# power.net
KiCad netlist of a schematic drawn in Altium Designer
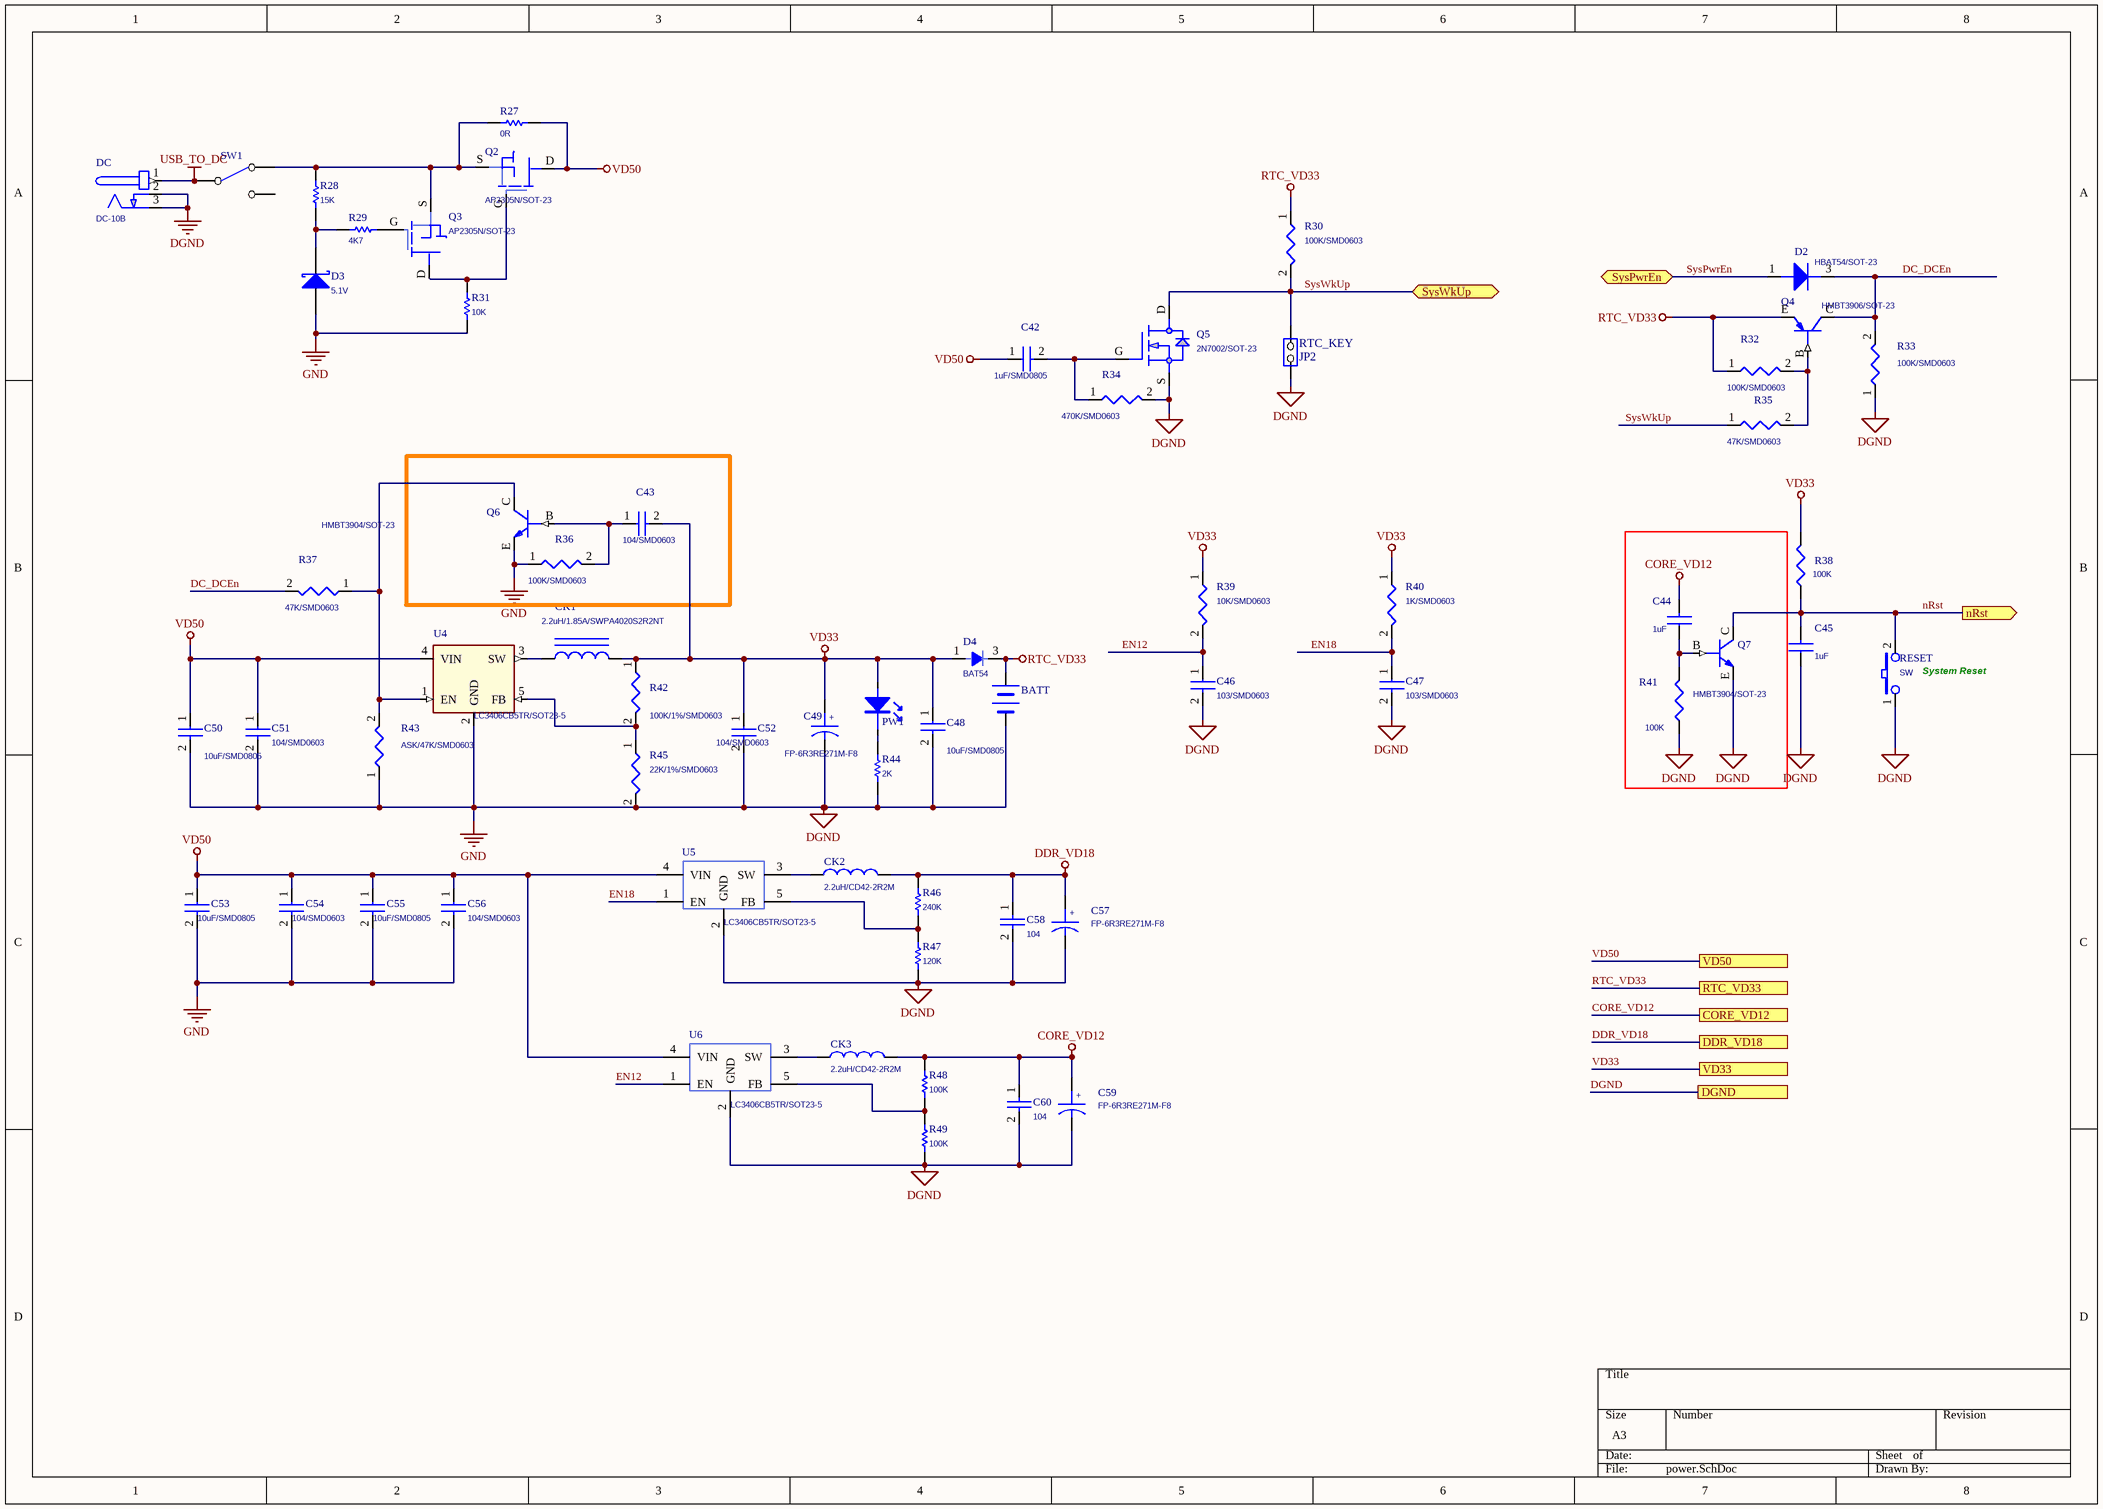
[diagram p0: power.SchDoc]

(export (version "E")
  (design (tool "Eeschema 10.0.6"))
  (components
    (comp (ref "BATT") (value "BATTERY") (footprint "MS621") (libsource (lib "GT2440原理图库") (part "BATTERY")))
    (comp (ref "C42") (value "1uF/SMD0805") (footprint "C0805") (libsource (lib "*") (part "C/SMD0805")))
    (comp (ref "C43") (value "104/SMD0603") (footprint "0603C") (libsource (lib "*") (part "C/SMD0603")))
    (comp (ref "C44") (value "1uF") (footprint "0603C") (libsource (lib "*") (part "CAP NP_Dup1")))
    (comp (ref "C45") (value "1uF") (footprint "0603C") (libsource (lib "*") (part "CAP NP_Dup1")))
    (comp (ref "C46") (value "103/SMD0603") (footprint "0603C") (libsource (lib "*") (part "C/SMD0603")))
    (comp (ref "C47") (value "103/SMD0603") (footprint "0603C") (libsource (lib "*") (part "C/SMD0603")))
    (comp (ref "C48") (value "10uF/SMD0805") (footprint "C0805") (libsource (lib "*") (part "C/SMD0805")))
    (comp (ref "C49")
      (value "FP-6R3RE271M-F8")
      (footprint "6R3RE271M")
      (libsource (lib "*") (part "CAP POL"))
    )
    (comp (ref "C50") (value "10uF/SMD0805") (footprint "C0805") (libsource (lib "*") (part "C/SMD0805")))
    (comp (ref "C51") (value "104/SMD0603") (footprint "0603C") (libsource (lib "*") (part "C/SMD0603")))
    (comp (ref "C52") (value "104/SMD0603") (footprint "0603C") (libsource (lib "*") (part "C/SMD0603")))
    (comp (ref "C53") (value "10uF/SMD0805") (footprint "C0805") (libsource (lib "*") (part "C/SMD1206")))
    (comp (ref "C54") (value "104/SMD0603") (footprint "0603C") (libsource (lib "*") (part "C/SMD0603")))
    (comp (ref "C55") (value "10uF/SMD0805") (footprint "C0805") (libsource (lib "*") (part "C/SMD1206")))
    (comp (ref "C56") (value "104/SMD0603") (footprint "0603C") (libsource (lib "*") (part "C/SMD0603")))
    (comp (ref "C57")
      (value "FP-6R3RE271M-F8")
      (footprint "6R3RE271M")
      (libsource (lib "*") (part "CAP POL"))
    )
    (comp (ref "C58")
      (value "104")
      (footprint "0603C")
      (description "Capacitor")
      (libsource (lib "MYSTM32") (part "CAP"))
    )
    (comp (ref "C59")
      (value "FP-6R3RE271M-F8")
      (footprint "6R3RE271M")
      (libsource (lib "*") (part "CAP POL"))
    )
    (comp (ref "C60")
      (value "104")
      (footprint "0603C")
      (description "Capacitor")
      (libsource (lib "MYSTM32") (part "CAP"))
    )
    (comp (ref "CK1")
      (value "2.2uH/1.85A/SWPA4020S2R2NT")
      (footprint "C1210_M")
      (libsource (lib "*") (part "INDUCTOR IRON"))
    )
    (comp (ref "CK2")
      (value "2.2uH/CD42-2R2M")
      (footprint "C1210_M")
      (libsource (lib "GT2440原理图库") (part "INDUCTOR1"))
    )
    (comp (ref "CK3")
      (value "2.2uH/CD42-2R2M")
      (footprint "C1210_M")
      (libsource (lib "GT2440原理图库") (part "INDUCTOR1"))
    )
    (comp (ref "D2") (value "HBAT54/SOT-23") (libsource (lib "changyong") (part "HBAT54/SOT-23")))
    (comp (ref "D3")
      (value "5.1V")
      (footprint "SOD-123_1N5819HW")
      (description "Schottky Rectifier")
      (fields (field (name "PUBLISHER") "Altium Limited"))
      (libsource (lib "Miscellaneous Devices") (part "Diode 10TQ035"))
    )
    (comp (ref "D4") (value "BAT54") (footprint "BAT54") (libsource (lib "n32905") (part "BAT54")))
    (comp (ref "DC") (value "DC-10B") (footprint "DC-JACK") (libsource (lib "STM32F107VCT") (part "PJ202A")))
    (comp (ref "PW1") (value "red") (footprint "LED-0603") (libsource (lib "GT2440原理图库") (part "LED")))
    (comp (ref "Q2")
      (value "AP2305N/SOT-23")
      (footprint "AP2305N_SOT23")
      (libsource (lib "changyong") (part "AP2305N/SOT-23"))
    )
    (comp (ref "Q3")
      (value "AP2305N/SOT-23")
      (footprint "AP2305N_SOT23")
      (libsource (lib "changyong") (part "AP2305N/SOT-23"))
    )
    (comp (ref "Q4")
      (value "HMBT3906/SOT-23")
      (footprint "SOT-23_HMBT3906")
      (libsource (lib "*") (part "HMBT3906/SOT-23"))
    )
    (comp (ref "Q5")
      (value "2N7002/SOT-23")
      (footprint "SOT-23_H2N7002")
      (libsource (lib "*") (part "2N7002/SOT-23_Dup1"))
    )
    (comp (ref "Q6")
      (value "HMBT3904/SOT-23")
      (footprint "SOT-23_HMBT3904")
      (libsource (lib "*") (part "HMBT3904/SOT-23"))
    )
    (comp (ref "Q7")
      (value "HMBT3904/SOT-23")
      (footprint "SOT-23_HMBT3904")
      (libsource (lib "changyong") (part "HMBT3904/SOT-23"))
    )
    (comp (ref "R27")
      (value "0R")
      (footprint "0603C")
      (description "Resistor")
      (fields (field (name "PUBLISHER") "Altium Limited"))
      (libsource (lib "STM32F107VCT") (part "res1"))
    )
    (comp (ref "R28")
      (value "15K")
      (footprint "0603C")
      (description "Resistor")
      (fields (field (name "PUBLISHER") "Altium Limited"))
      (libsource (lib "STM32F107VCT") (part "res1"))
    )
    (comp (ref "R29")
      (value "4K7")
      (footprint "0603C")
      (description "Resistor")
      (fields (field (name "PUBLISHER") "Altium Limited"))
      (libsource (lib "STM32F107VCT") (part "res1"))
    )
    (comp (ref "R30") (value "100K/SMD0603") (footprint "0603R") (libsource (lib "*") (part "R/SMD0603")))
    (comp (ref "R31")
      (value "10K")
      (footprint "0603C")
      (description "Resistor")
      (fields (field (name "PUBLISHER") "Altium Limited"))
      (libsource (lib "STM32F107VCT") (part "res1"))
    )
    (comp (ref "R32") (value "100K/SMD0603") (footprint "0603R") (libsource (lib "*") (part "R/SMD0603")))
    (comp (ref "R33") (value "100K/SMD0603") (footprint "0603R") (libsource (lib "*") (part "R/SMD0603")))
    (comp (ref "R34") (value "470K/SMD0603") (footprint "0603R") (libsource (lib "*") (part "R/SMD0603")))
    (comp (ref "R35") (value "47K/SMD0603") (footprint "0603R") (libsource (lib "*") (part "R/SMD0603")))
    (comp (ref "R36") (value "100K/SMD0603") (footprint "0603R") (libsource (lib "*") (part "R/SMD0603")))
    (comp (ref "R37") (value "47K/SMD0603") (footprint "0603R") (libsource (lib "*") (part "R/SMD0603")))
    (comp (ref "R38") (value "100K") (footprint "0603R") (libsource (lib "*") (part "R_Dup1")))
    (comp (ref "R39") (value "10K/SMD0603") (footprint "0603R") (libsource (lib "*") (part "R/SMD0603")))
    (comp (ref "R40") (value "1K/SMD0603") (footprint "0603R") (libsource (lib "*") (part "R/SMD0603")))
    (comp (ref "R41") (value "100K") (footprint "0603R") (libsource (lib "*") (part "R_Dup1")))
    (comp (ref "R42") (value "100K/1%/SMD0603") (footprint "0603R") (libsource (lib "*") (part "R/SMD0603")))
    (comp (ref "R43") (value "ASK/47K/SMD0603") (footprint "0603R") (libsource (lib "*") (part "R/SMD0603")))
    (comp (ref "R44")
      (value "2K")
      (footprint "0603R")
      (description "Resistor")
      (fields (field (name "PUBLISHER") "Altium Limited"))
      (libsource (lib "STM32F107VCT") (part "res1"))
    )
    (comp (ref "R45") (value "22K/1%/SMD0603") (footprint "0603R") (libsource (lib "*") (part "R/SMD0603")))
    (comp (ref "R46")
      (value "240K")
      (footprint "0603R")
      (description "Resistor")
      (fields (field (name "PUBLISHER") "Altium Limited"))
      (libsource (lib "STM32F107VCT") (part "res1"))
    )
    (comp (ref "R47")
      (value "120K")
      (footprint "0603R")
      (description "Resistor")
      (fields (field (name "PUBLISHER") "Altium Limited"))
      (libsource (lib "STM32F107VCT") (part "res1"))
    )
    (comp (ref "R48")
      (value "100K")
      (footprint "0603R")
      (description "Resistor")
      (fields (field (name "PUBLISHER") "Altium Limited"))
      (libsource (lib "STM32F107VCT") (part "res1"))
    )
    (comp (ref "R49")
      (value "100K")
      (footprint "0603R")
      (description "Resistor")
      (fields (field (name "PUBLISHER") "Altium Limited"))
      (libsource (lib "STM32F107VCT") (part "res1"))
    )
    (comp (ref "RESET") (value "SW") (footprint "SW-PB2") (libsource (lib "GT2440原理图库") (part "SW_PUSH")))
    (comp (ref "RTC_KEY") (value "JP2") (footprint "mhdr1x2") (libsource (lib "STM32F103VBH6") (part "JP2")))
    (comp (ref "SW1") (value "~") (footprint "SS-12D07") (libsource (lib "GT2440原理图库") (part "SW SPDT")))
    (comp (ref "U4")
      (value "LC3406CB5TR/SOT23-5")
      (footprint "SOT-23-5")
      (libsource (lib "*") (part "LC3406CB5TR/SOT23-5"))
    )
    (comp (ref "U5")
      (value "LC3406CB5TR/SOT23-5")
      (footprint "SOT-23-5")
      (libsource (lib "n32905") (part "LC3406CB5TR/SOT23-5"))
    )
    (comp (ref "U6")
      (value "LC3406CB5TR/SOT23-5")
      (footprint "SOT-23-5")
      (libsource (lib "n32905") (part "LC3406CB5TR/SOT23-5"))
    )
  )
  (nets
    (net (code "1") (name "/DC_DCEn") (class "Default")
      (node (ref "D2") (pin "3") (pinfunction "3_3") (pintype "passive"))
      (node (ref "Q4") (pin "C") (pinfunction "COLLECTOR_C") (pintype "passive"))
      (node (ref "R33") (pin "2") (pinfunction "2_2") (pintype "passive"))
      (node (ref "R37") (pin "2") (pinfunction "2_2") (pintype "passive"))
    )
    (net (code "2") (name "/EN12") (class "Default")
      (node (ref "C46") (pin "1") (pinfunction "1_1") (pintype "passive"))
      (node (ref "R39") (pin "2") (pinfunction "2_2") (pintype "passive"))
      (node (ref "U6") (pin "1") (pinfunction "EN_1") (pintype "passive"))
    )
    (net (code "3") (name "/EN18") (class "Default")
      (node (ref "C47") (pin "1") (pinfunction "1_1") (pintype "passive"))
      (node (ref "R40") (pin "2") (pinfunction "2_2") (pintype "passive"))
      (node (ref "U5") (pin "1") (pinfunction "EN_1") (pintype "passive"))
    )
    (net (code "4") (name "/SysPwrEn") (class "Default")
      (node (ref "D2") (pin "1") (pinfunction "1_1") (pintype "passive"))
    )
    (net (code "5") (name "/SysWkUp") (class "Default")
      (node (ref "Q5") (pin "D") (pinfunction "D_D") (pintype "passive"))
      (node (ref "R30") (pin "2") (pinfunction "2_2") (pintype "passive"))
      (node (ref "R35") (pin "1") (pinfunction "1_1") (pintype "passive"))
      (node (ref "RTC_KEY") (pin "2") (pinfunction "NO_2") (pintype "passive"))
    )
    (net (code "6") (name "/nRst") (class "Default")
      (node (ref "C45") (pin "2") (pinfunction "2_2") (pintype "passive"))
      (node (ref "Q7") (pin "C") (pinfunction "COLLECTOR_C") (pintype "passive"))
      (node (ref "R38") (pin "2") (pinfunction "2_2") (pintype "passive"))
      (node (ref "RESET") (pin "2") (pinfunction "2_2") (pintype "passive"))
    )
    (net (code "7") (name "CORE_VD12") (class "Default")
      (node (ref "C44") (pin "2") (pinfunction "2_2") (pintype "passive"))
      (node (ref "C59") (pin "1") (pinfunction "1_1") (pintype "passive"))
      (node (ref "C60") (pin "1") (pinfunction "1_1") (pintype "passive"))
      (node (ref "CK3") (pin "2") (pinfunction "2_2") (pintype "passive"))
      (node (ref "R48") (pin "2") (pinfunction "2_2") (pintype "passive"))
    )
    (net (code "8") (name "DDR_VD18") (class "Default")
      (node (ref "C57") (pin "1") (pinfunction "1_1") (pintype "passive"))
      (node (ref "C58") (pin "1") (pinfunction "1_1") (pintype "passive"))
      (node (ref "CK2") (pin "2") (pinfunction "2_2") (pintype "passive"))
      (node (ref "R46") (pin "2") (pinfunction "2_2") (pintype "passive"))
    )
    (net (code "9") (name "DGND") (class "Default")
      (node (ref "BATT") (pin "2") (pintype "passive"))
      (node (ref "C45") (pin "1") (pinfunction "1_1") (pintype "passive"))
      (node (ref "C46") (pin "2") (pinfunction "2_2") (pintype "passive"))
      (node (ref "C47") (pin "2") (pinfunction "2_2") (pintype "passive"))
      (node (ref "C48") (pin "2") (pinfunction "2_2") (pintype "passive"))
      (node (ref "C49") (pin "2") (pinfunction "2_2") (pintype "passive"))
      (node (ref "C50") (pin "2") (pinfunction "2_2") (pintype "passive"))
      (node (ref "C51") (pin "2") (pinfunction "2_2") (pintype "passive"))
      (node (ref "C52") (pin "2") (pinfunction "2_2") (pintype "passive"))
      (node (ref "C53") (pin "2") (pinfunction "2_2") (pintype "passive"))
      (node (ref "C54") (pin "2") (pinfunction "2_2") (pintype "passive"))
      (node (ref "C55") (pin "2") (pinfunction "2_2") (pintype "passive"))
      (node (ref "C56") (pin "2") (pinfunction "2_2") (pintype "passive"))
      (node (ref "C57") (pin "2") (pinfunction "2_2") (pintype "passive"))
      (node (ref "C58") (pin "2") (pinfunction "2_2") (pintype "passive"))
      (node (ref "C59") (pin "2") (pinfunction "2_2") (pintype "passive"))
      (node (ref "C60") (pin "2") (pinfunction "2_2") (pintype "passive"))
      (node (ref "D3") (pin "2") (pinfunction "A_2") (pintype "passive"))
      (node (ref "DC") (pin "2") (pinfunction "GND_2") (pintype "passive"))
      (node (ref "DC") (pin "3") (pinfunction "GND_3") (pintype "passive"))
      (node (ref "Q5") (pin "S") (pinfunction "S_S") (pintype "passive"))
      (node (ref "Q6") (pin "E") (pinfunction "EMITTER_E") (pintype "passive"))
      (node (ref "Q7") (pin "E") (pinfunction "EMITTER_E") (pintype "passive"))
      (node (ref "R31") (pin "1") (pinfunction "1_1") (pintype "passive"))
      (node (ref "R33") (pin "1") (pinfunction "1_1") (pintype "passive"))
      (node (ref "R34") (pin "2") (pinfunction "2_2") (pintype "passive"))
      (node (ref "R36") (pin "1") (pinfunction "1_1") (pintype "passive"))
      (node (ref "R41") (pin "2") (pinfunction "2_2") (pintype "passive"))
      (node (ref "R43") (pin "1") (pinfunction "1_1") (pintype "passive"))
      (node (ref "R44") (pin "1") (pinfunction "1_1") (pintype "passive"))
      (node (ref "R45") (pin "2") (pinfunction "2_2") (pintype "passive"))
      (node (ref "R47") (pin "1") (pinfunction "1_1") (pintype "passive"))
      (node (ref "R49") (pin "1") (pinfunction "1_1") (pintype "passive"))
      (node (ref "RESET") (pin "1") (pinfunction "1_1") (pintype "passive"))
      (node (ref "RTC_KEY") (pin "1") (pinfunction "COMMON_1") (pintype "passive"))
      (node (ref "U4") (pin "2") (pinfunction "GND_2") (pintype "power_in"))
      (node (ref "U5") (pin "2") (pinfunction "GND_2") (pintype "passive"))
      (node (ref "U6") (pin "2") (pinfunction "GND_2") (pintype "passive"))
    )
    (net (code "10") (name "Net-(C42-Pad2)") (class "Default")
      (node (ref "C42") (pin "2") (pinfunction "2_2") (pintype "passive"))
      (node (ref "Q5") (pin "G") (pinfunction "G_G") (pintype "passive"))
      (node (ref "R34") (pin "1") (pinfunction "1_1") (pintype "passive"))
    )
    (net (code "11") (name "Net-(D3-K)") (class "Default")
      (node (ref "D3") (pin "1") (pinfunction "K_1") (pintype "passive"))
      (node (ref "R28") (pin "1") (pinfunction "1_1") (pintype "passive"))
      (node (ref "R29") (pin "2") (pinfunction "2_2") (pintype "passive"))
    )
    (net (code "12") (name "Net-(PW1-Pad2)") (class "Default")
      (node (ref "PW1") (pin "2") (pinfunction "2_2") (pintype "passive"))
      (node (ref "R44") (pin "2") (pinfunction "2_2") (pintype "passive"))
    )
    (net (code "13") (name "Net-(Q2-2)") (class "Default")
      (node (ref "Q2") (pin "G") (pinfunction "2_G") (pintype "passive"))
      (node (ref "Q3") (pin "D") (pinfunction "1_D") (pintype "passive"))
      (node (ref "R31") (pin "2") (pinfunction "2_2") (pintype "passive"))
    )
    (net (code "14") (name "Net-(Q2-3)") (class "Default")
      (node (ref "Q2") (pin "S") (pinfunction "3_S") (pintype "passive"))
      (node (ref "Q3") (pin "S") (pinfunction "3_S") (pintype "passive"))
      (node (ref "R27") (pin "2") (pinfunction "2_2") (pintype "passive"))
      (node (ref "R28") (pin "2") (pinfunction "2_2") (pintype "passive"))
      (node (ref "SW1") (pin "2") (pinfunction "NC_2") (pintype "passive"))
    )
    (net (code "15") (name "Net-(Q3-2)") (class "Default")
      (node (ref "Q3") (pin "G") (pinfunction "2_G") (pintype "passive"))
      (node (ref "R29") (pin "1") (pinfunction "1_1") (pintype "passive"))
    )
    (net (code "16") (name "Net-(Q4-BASE)") (class "Default")
      (node (ref "Q4") (pin "B") (pinfunction "BASE_B") (pintype "input"))
      (node (ref "R32") (pin "2") (pinfunction "2_2") (pintype "passive"))
      (node (ref "R35") (pin "2") (pinfunction "2_2") (pintype "passive"))
    )
    (net (code "17") (name "Net-(Q6-BASE)") (class "Default")
      (node (ref "C43") (pin "1") (pinfunction "1_1") (pintype "passive"))
      (node (ref "Q6") (pin "B") (pinfunction "BASE_B") (pintype "input"))
      (node (ref "R36") (pin "2") (pinfunction "2_2") (pintype "passive"))
    )
    (net (code "18") (name "Net-(Q6-COLLECTOR)") (class "Default")
      (node (ref "Q6") (pin "C") (pinfunction "COLLECTOR_C") (pintype "passive"))
      (node (ref "R37") (pin "1") (pinfunction "1_1") (pintype "passive"))
      (node (ref "R43") (pin "2") (pinfunction "2_2") (pintype "passive"))
      (node (ref "U4") (pin "1") (pinfunction "EN_1") (pintype "input"))
    )
    (net (code "19") (name "Net-(Q7-BASE)") (class "Default")
      (node (ref "C44") (pin "1") (pinfunction "1_1") (pintype "passive"))
      (node (ref "Q7") (pin "B") (pinfunction "BASE_B") (pintype "input"))
      (node (ref "R41") (pin "1") (pinfunction "1_1") (pintype "passive"))
    )
    (net (code "20") (name "Net-(U4-FB)") (class "Default")
      (node (ref "R42") (pin "2") (pinfunction "2_2") (pintype "passive"))
      (node (ref "R45") (pin "1") (pinfunction "1_1") (pintype "passive"))
      (node (ref "U4") (pin "5") (pinfunction "FB_5") (pintype "input"))
    )
    (net (code "21") (name "Net-(U4-SW)") (class "Default")
      (node (ref "CK1") (pin "1") (pinfunction "1_1") (pintype "passive"))
      (node (ref "U4") (pin "3") (pinfunction "SW_3") (pintype "output"))
    )
    (net (code "22") (name "Net-(U5-FB)") (class "Default")
      (node (ref "R46") (pin "1") (pinfunction "1_1") (pintype "passive"))
      (node (ref "R47") (pin "2") (pinfunction "2_2") (pintype "passive"))
      (node (ref "U5") (pin "5") (pinfunction "FB_5") (pintype "passive"))
    )
    (net (code "23") (name "Net-(U5-SW)") (class "Default")
      (node (ref "CK2") (pin "1") (pinfunction "1_1") (pintype "passive"))
      (node (ref "U5") (pin "3") (pinfunction "SW_3") (pintype "passive"))
    )
    (net (code "24") (name "Net-(U6-FB)") (class "Default")
      (node (ref "R48") (pin "1") (pinfunction "1_1") (pintype "passive"))
      (node (ref "R49") (pin "2") (pinfunction "2_2") (pintype "passive"))
      (node (ref "U6") (pin "5") (pinfunction "FB_5") (pintype "passive"))
    )
    (net (code "25") (name "Net-(U6-SW)") (class "Default")
      (node (ref "CK3") (pin "1") (pinfunction "1_1") (pintype "passive"))
      (node (ref "U6") (pin "3") (pinfunction "SW_3") (pintype "passive"))
    )
    (net (code "26") (name "RTC_VD33") (class "Default")
      (node (ref "BATT") (pin "1") (pintype "passive"))
      (node (ref "D4") (pin "3") (pinfunction "3_3") (pintype "passive"))
      (node (ref "Q4") (pin "E") (pinfunction "EMITTER_E") (pintype "passive"))
      (node (ref "R30") (pin "1") (pinfunction "1_1") (pintype "passive"))
      (node (ref "R32") (pin "1") (pinfunction "1_1") (pintype "passive"))
    )
    (net (code "27") (name "USB_TO_DC") (class "Default")
      (node (ref "DC") (pin "1") (pinfunction "+_1") (pintype "output"))
      (node (ref "SW1") (pin "1") (pinfunction "COMMON_1") (pintype "passive"))
    )
    (net (code "28") (name "VD33") (class "Default")
      (node (ref "C43") (pin "2") (pinfunction "2_2") (pintype "passive"))
      (node (ref "C48") (pin "1") (pinfunction "1_1") (pintype "passive"))
      (node (ref "C49") (pin "1") (pinfunction "1_1") (pintype "passive"))
      (node (ref "C52") (pin "1") (pinfunction "1_1") (pintype "passive"))
      (node (ref "CK1") (pin "2") (pinfunction "2_2") (pintype "passive"))
      (node (ref "D4") (pin "1") (pinfunction "1_1") (pintype "passive"))
      (node (ref "PW1") (pin "1") (pinfunction "1_1") (pintype "passive"))
      (node (ref "R38") (pin "1") (pinfunction "1_1") (pintype "passive"))
      (node (ref "R39") (pin "1") (pinfunction "1_1") (pintype "passive"))
      (node (ref "R40") (pin "1") (pinfunction "1_1") (pintype "passive"))
      (node (ref "R42") (pin "1") (pinfunction "1_1") (pintype "passive"))
    )
    (net (code "29") (name "VD50") (class "Default")
      (node (ref "C42") (pin "1") (pinfunction "1_1") (pintype "passive"))
      (node (ref "C50") (pin "1") (pinfunction "1_1") (pintype "passive"))
      (node (ref "C51") (pin "1") (pinfunction "1_1") (pintype "passive"))
      (node (ref "C53") (pin "1") (pinfunction "1_1") (pintype "passive"))
      (node (ref "C54") (pin "1") (pinfunction "1_1") (pintype "passive"))
      (node (ref "C55") (pin "1") (pinfunction "1_1") (pintype "passive"))
      (node (ref "C56") (pin "1") (pinfunction "1_1") (pintype "passive"))
      (node (ref "Q2") (pin "D") (pinfunction "1_D") (pintype "passive"))
      (node (ref "R27") (pin "1") (pinfunction "1_1") (pintype "passive"))
      (node (ref "U4") (pin "4") (pinfunction "VIN_4") (pintype "power_in"))
      (node (ref "U5") (pin "4") (pinfunction "VIN_4") (pintype "passive"))
      (node (ref "U6") (pin "4") (pinfunction "VIN_4") (pintype "passive"))
    )
    (net (code "30") (name "unconnected-(SW1-NO-Pad3)") (class "Default")
      (node (ref "SW1") (pin "3") (pinfunction "NO_3") (pintype "passive"))
    )
  )
)
